# Moteino.net
KiCad netlist of a schematic drawn in EAGLE
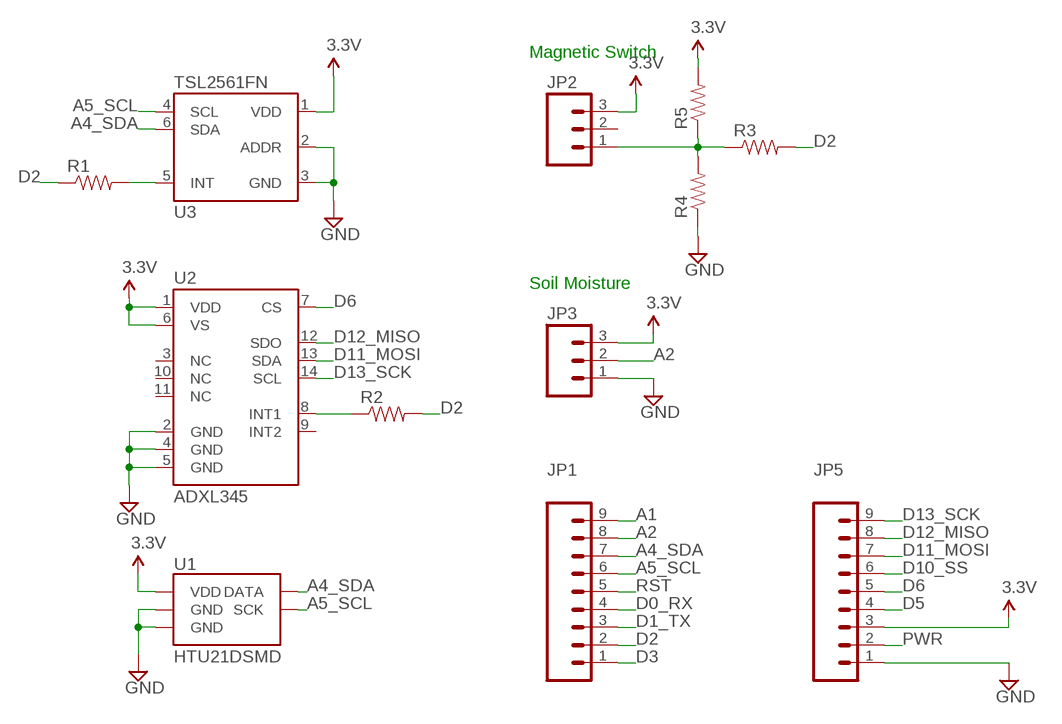
[diagram p0: schematic, sheet 1]

(export (version "E")
  (design (tool "Eeschema 10.0.6"))
  (components
    (comp (ref "JP1")
      (value "M09")
      (footprint "eagle-import:1X09")
      (libsource (lib "eagle-import") (part "M09"))
    )
    (comp (ref "JP2")
      (value "M03PTH")
      (footprint "eagle-import:1X03")
      (libsource (lib "eagle-import") (part "M03PTH"))
    )
    (comp (ref "JP3")
      (value "M03PTH")
      (footprint "eagle-import:1X03")
      (libsource (lib "eagle-import") (part "M03PTH"))
    )
    (comp (ref "JP5")
      (value "M09")
      (footprint "eagle-import:1X09")
      (libsource (lib "eagle-import") (part "M09"))
    )
    (comp (ref "R1")
      (value "RESISTOR0603-RES")
      (footprint "eagle-import:0603-RES")
      (libsource (lib "eagle-import") (part "RESISTOR0603-RES"))
    )
    (comp (ref "R2")
      (value "RESISTOR0603-RES")
      (footprint "eagle-import:0603-RES")
      (libsource (lib "eagle-import") (part "RESISTOR0603-RES"))
    )
    (comp (ref "R3")
      (value "RESISTOR0603-RES")
      (footprint "eagle-import:0603-RES")
      (libsource (lib "eagle-import") (part "RESISTOR0603-RES"))
    )
    (comp (ref "R4")
      (value "RESISTOR0603-RES")
      (footprint "eagle-import:0603-RES")
      (libsource (lib "eagle-import") (part "RESISTOR0603-RES"))
    )
    (comp (ref "R5")
      (value "RESISTOR0603-RES")
      (footprint "eagle-import:0603-RES")
      (libsource (lib "eagle-import") (part "RESISTOR0603-RES"))
    )
    (comp (ref "U1")
      (value "HTU21DSMD")
      (footprint "eagle-import:HTU21D")
      (libsource (lib "eagle-import") (part "HTU21DSMD"))
    )
    (comp (ref "U2")
      (value "ADXL345")
      (footprint "eagle-import:LGA14")
      (libsource (lib "eagle-import") (part "ADXL345"))
    )
    (comp (ref "U3")
      (value "TSL2561FN")
      (footprint "eagle-import:FN-6")
      (libsource (lib "eagle-import") (part "TSL2561FN"))
    )
  )
  (nets
    (net (code "1") (name "/A1") (class "Default")
      (node (ref "JP1") (pin "9") (pinfunction "9_9") (pintype "passive"))
    )
    (net (code "2") (name "/A2") (class "Default")
      (node (ref "JP1") (pin "8") (pinfunction "8_8") (pintype "passive"))
      (node (ref "JP3") (pin "2") (pinfunction "2_2") (pintype "passive"))
    )
    (net (code "3") (name "/A4_SDA") (class "Default")
      (node (ref "JP1") (pin "7") (pinfunction "7_7") (pintype "passive"))
      (node (ref "U1") (pin "DATA") (pinfunction "DATA_DATA") (pintype "bidirectional"))
      (node (ref "U3") (pin "6") (pinfunction "SDA_6") (pintype "bidirectional"))
    )
    (net (code "4") (name "/A5_SCL") (class "Default")
      (node (ref "JP1") (pin "6") (pinfunction "6_6") (pintype "passive"))
      (node (ref "U1") (pin "SCK") (pinfunction "SCK_SCK") (pintype "input"))
      (node (ref "U3") (pin "4") (pinfunction "SCL_4") (pintype "input"))
    )
    (net (code "5") (name "/D0_RX") (class "Default")
      (node (ref "JP1") (pin "4") (pinfunction "4_4") (pintype "passive"))
    )
    (net (code "6") (name "/D1_TX") (class "Default")
      (node (ref "JP1") (pin "3") (pinfunction "3_3") (pintype "passive"))
    )
    (net (code "7") (name "/D2") (class "Default")
      (node (ref "JP1") (pin "2") (pinfunction "2_2") (pintype "passive"))
      (node (ref "R1") (pin "1") (pinfunction "1_1") (pintype "passive"))
      (node (ref "R2") (pin "2") (pinfunction "2_2") (pintype "passive"))
      (node (ref "R3") (pin "2") (pinfunction "2_2") (pintype "passive"))
    )
    (net (code "8") (name "/D3") (class "Default")
      (node (ref "JP1") (pin "1") (pinfunction "1_1") (pintype "passive"))
    )
    (net (code "9") (name "/D5") (class "Default")
      (node (ref "JP5") (pin "4") (pinfunction "4_4") (pintype "passive"))
    )
    (net (code "10") (name "/D6") (class "Default")
      (node (ref "JP5") (pin "5") (pinfunction "5_5") (pintype "passive"))
      (node (ref "U2") (pin "7") (pinfunction "CS_7") (pintype "bidirectional"))
    )
    (net (code "11") (name "/D10_SS") (class "Default")
      (node (ref "JP5") (pin "6") (pinfunction "6_6") (pintype "passive"))
    )
    (net (code "12") (name "/D11_MOSI") (class "Default")
      (node (ref "JP5") (pin "7") (pinfunction "7_7") (pintype "passive"))
      (node (ref "U2") (pin "13") (pinfunction "SDA_13") (pintype "bidirectional"))
    )
    (net (code "13") (name "/D12_MISO") (class "Default")
      (node (ref "JP5") (pin "8") (pinfunction "8_8") (pintype "passive"))
      (node (ref "U2") (pin "12") (pinfunction "SDO_12") (pintype "bidirectional"))
    )
    (net (code "14") (name "/D13_SCK") (class "Default")
      (node (ref "JP5") (pin "9") (pinfunction "9_9") (pintype "passive"))
      (node (ref "U2") (pin "14") (pinfunction "SCL_14") (pintype "bidirectional"))
    )
    (net (code "15") (name "/PWR") (class "Default")
      (node (ref "JP5") (pin "2") (pinfunction "2_2") (pintype "passive"))
    )
    (net (code "16") (name "/RST") (class "Default")
      (node (ref "JP1") (pin "5") (pinfunction "5_5") (pintype "passive"))
    )
    (net (code "17") (name "3.3V") (class "Default")
      (node (ref "JP2") (pin "3") (pinfunction "3_3") (pintype "passive"))
      (node (ref "JP3") (pin "3") (pinfunction "3_3") (pintype "passive"))
      (node (ref "JP5") (pin "3") (pinfunction "3_3") (pintype "passive"))
      (node (ref "R5") (pin "2") (pinfunction "2_2") (pintype "passive"))
      (node (ref "U1") (pin "VDD") (pinfunction "VDD_VDD") (pintype "power_in"))
      (node (ref "U2") (pin "1") (pinfunction "VDD_1") (pintype "bidirectional"))
      (node (ref "U2") (pin "6") (pinfunction "VS_6") (pintype "bidirectional"))
      (node (ref "U3") (pin "1") (pinfunction "VDD_1") (pintype "power_in"))
    )
    (net (code "18") (name "GND") (class "Default")
      (node (ref "JP3") (pin "1") (pinfunction "1_1") (pintype "passive"))
      (node (ref "JP5") (pin "1") (pinfunction "1_1") (pintype "passive"))
      (node (ref "R4") (pin "1") (pinfunction "1_1") (pintype "passive"))
      (node (ref "U1") (pin "7") (pinfunction "GND_7") (pintype "power_in"))
      (node (ref "U1") (pin "GND") (pinfunction "GND_GND") (pintype "power_in"))
      (node (ref "U2") (pin "2") (pinfunction "GND_2") (pintype "bidirectional"))
      (node (ref "U2") (pin "4") (pinfunction "GND_4") (pintype "bidirectional"))
      (node (ref "U2") (pin "5") (pinfunction "GND_5") (pintype "bidirectional"))
      (node (ref "U3") (pin "2") (pinfunction "ADDR_2") (pintype "input"))
      (node (ref "U3") (pin "3") (pinfunction "GND_3") (pintype "power_in"))
    )
    (net (code "19") (name "Net-(JP2-Pad1)") (class "Default")
      (node (ref "JP2") (pin "1") (pinfunction "1_1") (pintype "passive"))
      (node (ref "R3") (pin "1") (pinfunction "1_1") (pintype "passive"))
      (node (ref "R4") (pin "2") (pinfunction "2_2") (pintype "passive"))
      (node (ref "R5") (pin "1") (pinfunction "1_1") (pintype "passive"))
    )
    (net (code "20") (name "Net-(U2-INT1)") (class "Default")
      (node (ref "R2") (pin "1") (pinfunction "1_1") (pintype "passive"))
      (node (ref "U2") (pin "8") (pinfunction "INT1_8") (pintype "bidirectional"))
    )
    (net (code "21") (name "Net-(U3-INT)") (class "Default")
      (node (ref "R1") (pin "2") (pinfunction "2_2") (pintype "passive"))
      (node (ref "U3") (pin "5") (pinfunction "INT_5") (pintype "output"))
    )
    (net (code "22") (name "unconnected-(JP2-Pad2)") (class "Default")
      (node (ref "JP2") (pin "2") (pinfunction "2_2") (pintype "passive"))
    )
    (net (code "23") (name "unconnected-(U2-INT2-Pad9)") (class "Default")
      (node (ref "U2") (pin "9") (pinfunction "INT2_9") (pintype "bidirectional"))
    )
    (net (code "24") (name "unconnected-(U2-NC-Pad3)") (class "Default")
      (node (ref "U2") (pin "3") (pinfunction "NC_3") (pintype "bidirectional"))
    )
    (net (code "25") (name "unconnected-(U2-NC-Pad10)") (class "Default")
      (node (ref "U2") (pin "10") (pinfunction "NC_10") (pintype "bidirectional"))
    )
    (net (code "26") (name "unconnected-(U2-NC-Pad11)") (class "Default")
      (node (ref "U2") (pin "11") (pinfunction "NC_11") (pintype "bidirectional"))
    )
  )
)
